# 2naprazdno.net
KiCad netlist of a schematic drawn in EAGLE
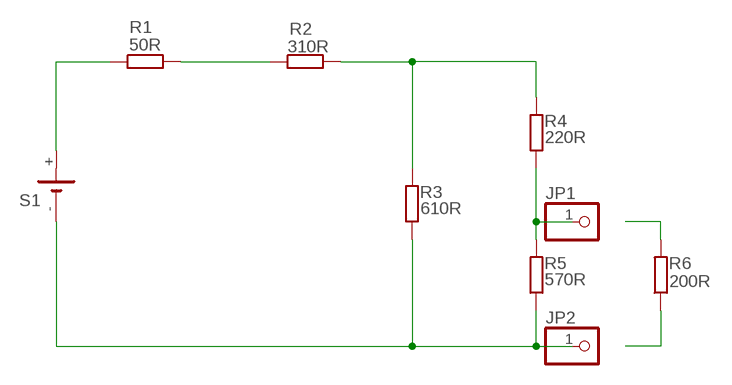
[diagram p0: schematic, sheet 1]

(export (version "E")
  (design (tool "Eeschema 10.0.6"))
  (components
    (comp (ref "JP1")
      (value "PINHD-1X1")
      (footprint "eagle-import:1X01")
      (libsource (lib "eagle-import") (part "PINHD-1X1"))
    )
    (comp (ref "JP2")
      (value "PINHD-1X1")
      (footprint "eagle-import:1X01")
      (libsource (lib "eagle-import") (part "PINHD-1X1"))
    )
    (comp (ref "R1")
      (value "50R")
      (footprint "eagle-import:0204_7")
      (libsource (lib "eagle-import") (part "R-EU_0204/7"))
    )
    (comp (ref "R2")
      (value "310R")
      (footprint "eagle-import:0204_7")
      (libsource (lib "eagle-import") (part "R-EU_0204/7"))
    )
    (comp (ref "R3")
      (value "610R")
      (footprint "eagle-import:0204_7")
      (libsource (lib "eagle-import") (part "R-EU_0204/7"))
    )
    (comp (ref "R4")
      (value "220R")
      (footprint "eagle-import:0204_7")
      (libsource (lib "eagle-import") (part "R-EU_0204/7"))
    )
    (comp (ref "R5")
      (value "570R")
      (footprint "eagle-import:0204_7")
      (libsource (lib "eagle-import") (part "R-EU_0204/7"))
    )
    (comp (ref "R6")
      (value "200R")
      (footprint "eagle-import:0204_7")
      (libsource (lib "eagle-import") (part "R-EU_0204/7"))
    )
    (comp (ref "S1")
      (value "CH291-1220LF")
      (footprint "eagle-import:CH291-1220LF")
      (libsource (lib "eagle-import") (part "CH291-1220LF"))
    )
  )
  (nets
    (net (code "1") (name "Net-(JP1-Pad1)") (class "Default")
      (node (ref "JP1") (pin "1") (pinfunction "1_1") (pintype "passive"))
      (node (ref "R4") (pin "1") (pinfunction "1_1") (pintype "passive"))
      (node (ref "R5") (pin "2") (pinfunction "2_2") (pintype "passive"))
    )
    (net (code "2") (name "Net-(JP2-Pad1)") (class "Default")
      (node (ref "JP2") (pin "1") (pinfunction "1_1") (pintype "passive"))
      (node (ref "R3") (pin "1") (pinfunction "1_1") (pintype "passive"))
      (node (ref "R5") (pin "1") (pinfunction "1_1") (pintype "passive"))
      (node (ref "S1") (pin "-") (pinfunction "-_-") (pintype "passive"))
    )
    (net (code "3") (name "Net-(R1-Pad1)") (class "Default")
      (node (ref "R1") (pin "1") (pinfunction "1_1") (pintype "passive"))
      (node (ref "S1") (pin "+") (pinfunction "+_+") (pintype "passive"))
    )
    (net (code "4") (name "Net-(R1-Pad2)") (class "Default")
      (node (ref "R1") (pin "2") (pinfunction "2_2") (pintype "passive"))
      (node (ref "R2") (pin "1") (pinfunction "1_1") (pintype "passive"))
    )
    (net (code "5") (name "Net-(R2-Pad2)") (class "Default")
      (node (ref "R2") (pin "2") (pinfunction "2_2") (pintype "passive"))
      (node (ref "R3") (pin "2") (pinfunction "2_2") (pintype "passive"))
      (node (ref "R4") (pin "2") (pinfunction "2_2") (pintype "passive"))
    )
    (net (code "6") (name "unconnected-(R6-Pad1)") (class "Default")
      (node (ref "R6") (pin "1") (pinfunction "1_1") (pintype "passive"))
    )
    (net (code "7") (name "unconnected-(R6-Pad2)") (class "Default")
      (node (ref "R6") (pin "2") (pinfunction "2_2") (pintype "passive"))
    )
  )
)
